# LSW_0_HCMS29_STM32L0.net
KiCad netlist of a schematic drawn in Altium Designer
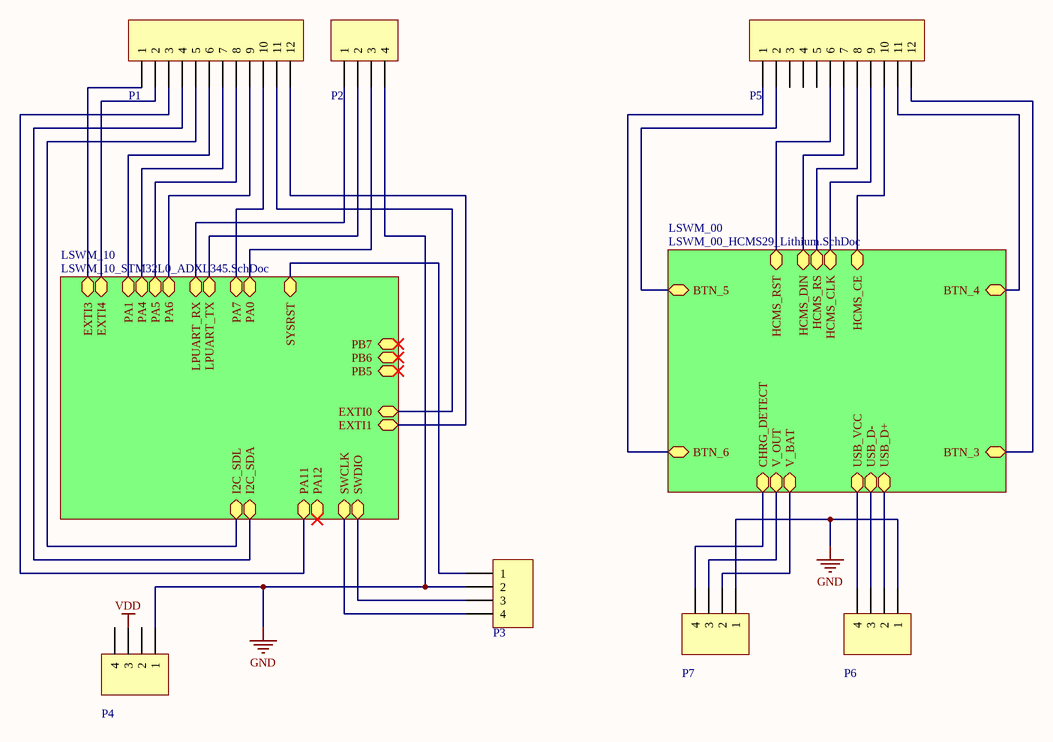
[diagram p0: LSW_0_HCMS29_STM32L0.SchDoc]

(export (version "E")
  (design (tool "Eeschema 10.0.6"))
  (components
    (comp (ref "P1")
      (value "Header 12")
      (footprint "HDR12X1_1.27mm")
      (description "接插件")
      (fields (field (name "PUBLISHER") "Altium Limited"))
      (libsource (lib "Schlib1") (part "Header 12"))
    )
    (comp (ref "P2")
      (value "Header 4")
      (footprint "HDR4X1_1.27mm")
      (description "接插件")
      (fields (field (name "PUBLISHER") "Altium Limited"))
      (libsource (lib "") (part "Header 4_1"))
    )
    (comp (ref "P3")
      (value "Header 4")
      (footprint "HDR4X1_1.27mm")
      (description "接插件")
      (fields (field (name "PUBLISHER") "Altium Limited"))
      (libsource (lib "") (part "Header 4_2"))
    )
    (comp (ref "P4")
      (value "Header 4")
      (footprint "HDR4X1_1.27mm")
      (description "接插件")
      (fields (field (name "PUBLISHER") "Altium Limited"))
      (libsource (lib "Schlib1") (part "Header 4"))
    )
    (comp (ref "P5")
      (value "Header 12")
      (footprint "HDR12X1_1.27mm")
      (description "接插件")
      (fields (field (name "PUBLISHER") "Altium Limited"))
      (libsource (lib "Schlib1") (part "Header 12"))
    )
    (comp (ref "P6")
      (value "Header 4")
      (footprint "HDR4X1_1.27mm")
      (description "接插件")
      (fields (field (name "PUBLISHER") "Altium Limited"))
      (libsource (lib "Schlib1") (part "Header 4"))
    )
    (comp (ref "P7")
      (value "Header 4")
      (footprint "HDR4X1_1.27mm")
      (description "接插件")
      (fields (field (name "PUBLISHER") "Altium Limited"))
      (libsource (lib "Schlib1") (part "Header 4"))
    )
  )
  (nets
    (net (code "1") (name "/BTN_3") (class "Default")
      (node (ref "P5") (pin "12") (pinfunction "12_12") (pintype "passive"))
    )
    (net (code "2") (name "/BTN_4") (class "Default")
      (node (ref "P5") (pin "11") (pinfunction "11_11") (pintype "passive"))
    )
    (net (code "3") (name "/BTN_5") (class "Default")
      (node (ref "P5") (pin "2") (pinfunction "2_2") (pintype "passive"))
    )
    (net (code "4") (name "/BTN_6") (class "Default")
      (node (ref "P5") (pin "1") (pinfunction "1_1") (pintype "passive"))
    )
    (net (code "5") (name "/CHRG_DETECT") (class "Default")
      (node (ref "P7") (pin "4") (pinfunction "4_4") (pintype "passive"))
    )
    (net (code "6") (name "/EXTI0") (class "Default")
      (node (ref "P1") (pin "11") (pinfunction "11_11") (pintype "passive"))
    )
    (net (code "7") (name "/EXTI1") (class "Default")
      (node (ref "P1") (pin "12") (pinfunction "12_12") (pintype "passive"))
    )
    (net (code "8") (name "/EXTI3") (class "Default")
      (node (ref "P1") (pin "1") (pinfunction "1_1") (pintype "passive"))
    )
    (net (code "9") (name "/EXTI4") (class "Default")
      (node (ref "P1") (pin "2") (pinfunction "2_2") (pintype "passive"))
    )
    (net (code "10") (name "/HCMS_CE") (class "Default")
      (node (ref "P5") (pin "10") (pinfunction "10_10") (pintype "passive"))
    )
    (net (code "11") (name "/HCMS_CLK") (class "Default")
      (node (ref "P5") (pin "9") (pinfunction "9_9") (pintype "passive"))
    )
    (net (code "12") (name "/HCMS_DIN") (class "Default")
      (node (ref "P5") (pin "7") (pinfunction "7_7") (pintype "passive"))
    )
    (net (code "13") (name "/HCMS_RS") (class "Default")
      (node (ref "P5") (pin "8") (pinfunction "8_8") (pintype "passive"))
    )
    (net (code "14") (name "/HCMS_RST") (class "Default")
      (node (ref "P5") (pin "6") (pinfunction "6_6") (pintype "passive"))
    )
    (net (code "15") (name "/I2C_SDA") (class "Default")
      (node (ref "P1") (pin "4") (pinfunction "4_4") (pintype "passive"))
    )
    (net (code "16") (name "/I2C_SDL") (class "Default")
      (node (ref "P1") (pin "5") (pinfunction "5_5") (pintype "passive"))
    )
    (net (code "17") (name "/LPUART_RX") (class "Default")
      (node (ref "P2") (pin "1") (pinfunction "1_1") (pintype "passive"))
    )
    (net (code "18") (name "/LPUART_TX") (class "Default")
      (node (ref "P2") (pin "2") (pinfunction "2_2") (pintype "passive"))
    )
    (net (code "19") (name "/PA0") (class "Default")
      (node (ref "P2") (pin "3") (pinfunction "3_3") (pintype "passive"))
    )
    (net (code "20") (name "/PA1") (class "Default")
      (node (ref "P1") (pin "6") (pinfunction "6_6") (pintype "passive"))
    )
    (net (code "21") (name "/PA4") (class "Default")
      (node (ref "P1") (pin "7") (pinfunction "7_7") (pintype "passive"))
    )
    (net (code "22") (name "/PA5") (class "Default")
      (node (ref "P1") (pin "8") (pinfunction "8_8") (pintype "passive"))
    )
    (net (code "23") (name "/PA6") (class "Default")
      (node (ref "P1") (pin "9") (pinfunction "9_9") (pintype "passive"))
    )
    (net (code "24") (name "/PA7") (class "Default")
      (node (ref "P1") (pin "10") (pinfunction "10_10") (pintype "passive"))
    )
    (net (code "25") (name "/PA11") (class "Default")
      (node (ref "P1") (pin "3") (pinfunction "3_3") (pintype "passive"))
    )
    (net (code "30") (name "/SWCLK") (class "Default")
      (node (ref "P3") (pin "4") (pinfunction "4_4") (pintype "passive"))
    )
    (net (code "31") (name "/SWDIO") (class "Default")
      (node (ref "P3") (pin "3") (pinfunction "3_3") (pintype "passive"))
    )
    (net (code "32") (name "/SYSRST") (class "Default")
      (node (ref "P3") (pin "1") (pinfunction "1_1") (pintype "passive"))
    )
    (net (code "33") (name "/USB_D+") (class "Default")
      (node (ref "P6") (pin "2") (pinfunction "2_2") (pintype "passive"))
    )
    (net (code "34") (name "/USB_D-") (class "Default")
      (node (ref "P6") (pin "3") (pinfunction "3_3") (pintype "passive"))
    )
    (net (code "35") (name "/USB_VCC") (class "Default")
      (node (ref "P6") (pin "4") (pinfunction "4_4") (pintype "passive"))
    )
    (net (code "36") (name "/V_BAT") (class "Default")
      (node (ref "P7") (pin "2") (pinfunction "2_2") (pintype "passive"))
    )
    (net (code "37") (name "/V_OUT") (class "Default")
      (node (ref "P7") (pin "3") (pinfunction "3_3") (pintype "passive"))
    )
    (net (code "38") (name "GND") (class "Default")
      (node (ref "P2") (pin "4") (pinfunction "4_4") (pintype "passive"))
      (node (ref "P3") (pin "2") (pinfunction "2_2") (pintype "passive"))
      (node (ref "P4") (pin "1") (pinfunction "1_1") (pintype "passive"))
      (node (ref "P6") (pin "1") (pinfunction "1_1") (pintype "passive"))
      (node (ref "P7") (pin "1") (pinfunction "1_1") (pintype "passive"))
    )
    (net (code "39") (name "VDD") (class "Default")
      (node (ref "P4") (pin "3") (pinfunction "3_3") (pintype "passive"))
    )
    (net (code "40") (name "unconnected-(P4-Pad2)") (class "Default")
      (node (ref "P4") (pin "2") (pinfunction "2_2") (pintype "passive"))
    )
    (net (code "41") (name "unconnected-(P4-Pad4)") (class "Default")
      (node (ref "P4") (pin "4") (pinfunction "4_4") (pintype "passive"))
    )
    (net (code "42") (name "unconnected-(P5-Pad3)") (class "Default")
      (node (ref "P5") (pin "3") (pinfunction "3_3") (pintype "passive"))
    )
    (net (code "43") (name "unconnected-(P5-Pad4)") (class "Default")
      (node (ref "P5") (pin "4") (pinfunction "4_4") (pintype "passive"))
    )
    (net (code "44") (name "unconnected-(P5-Pad5)") (class "Default")
      (node (ref "P5") (pin "5") (pinfunction "5_5") (pintype "passive"))
    )
  )
)
